# field_mill.net
KiCad netlist of a schematic drawn in EAGLE
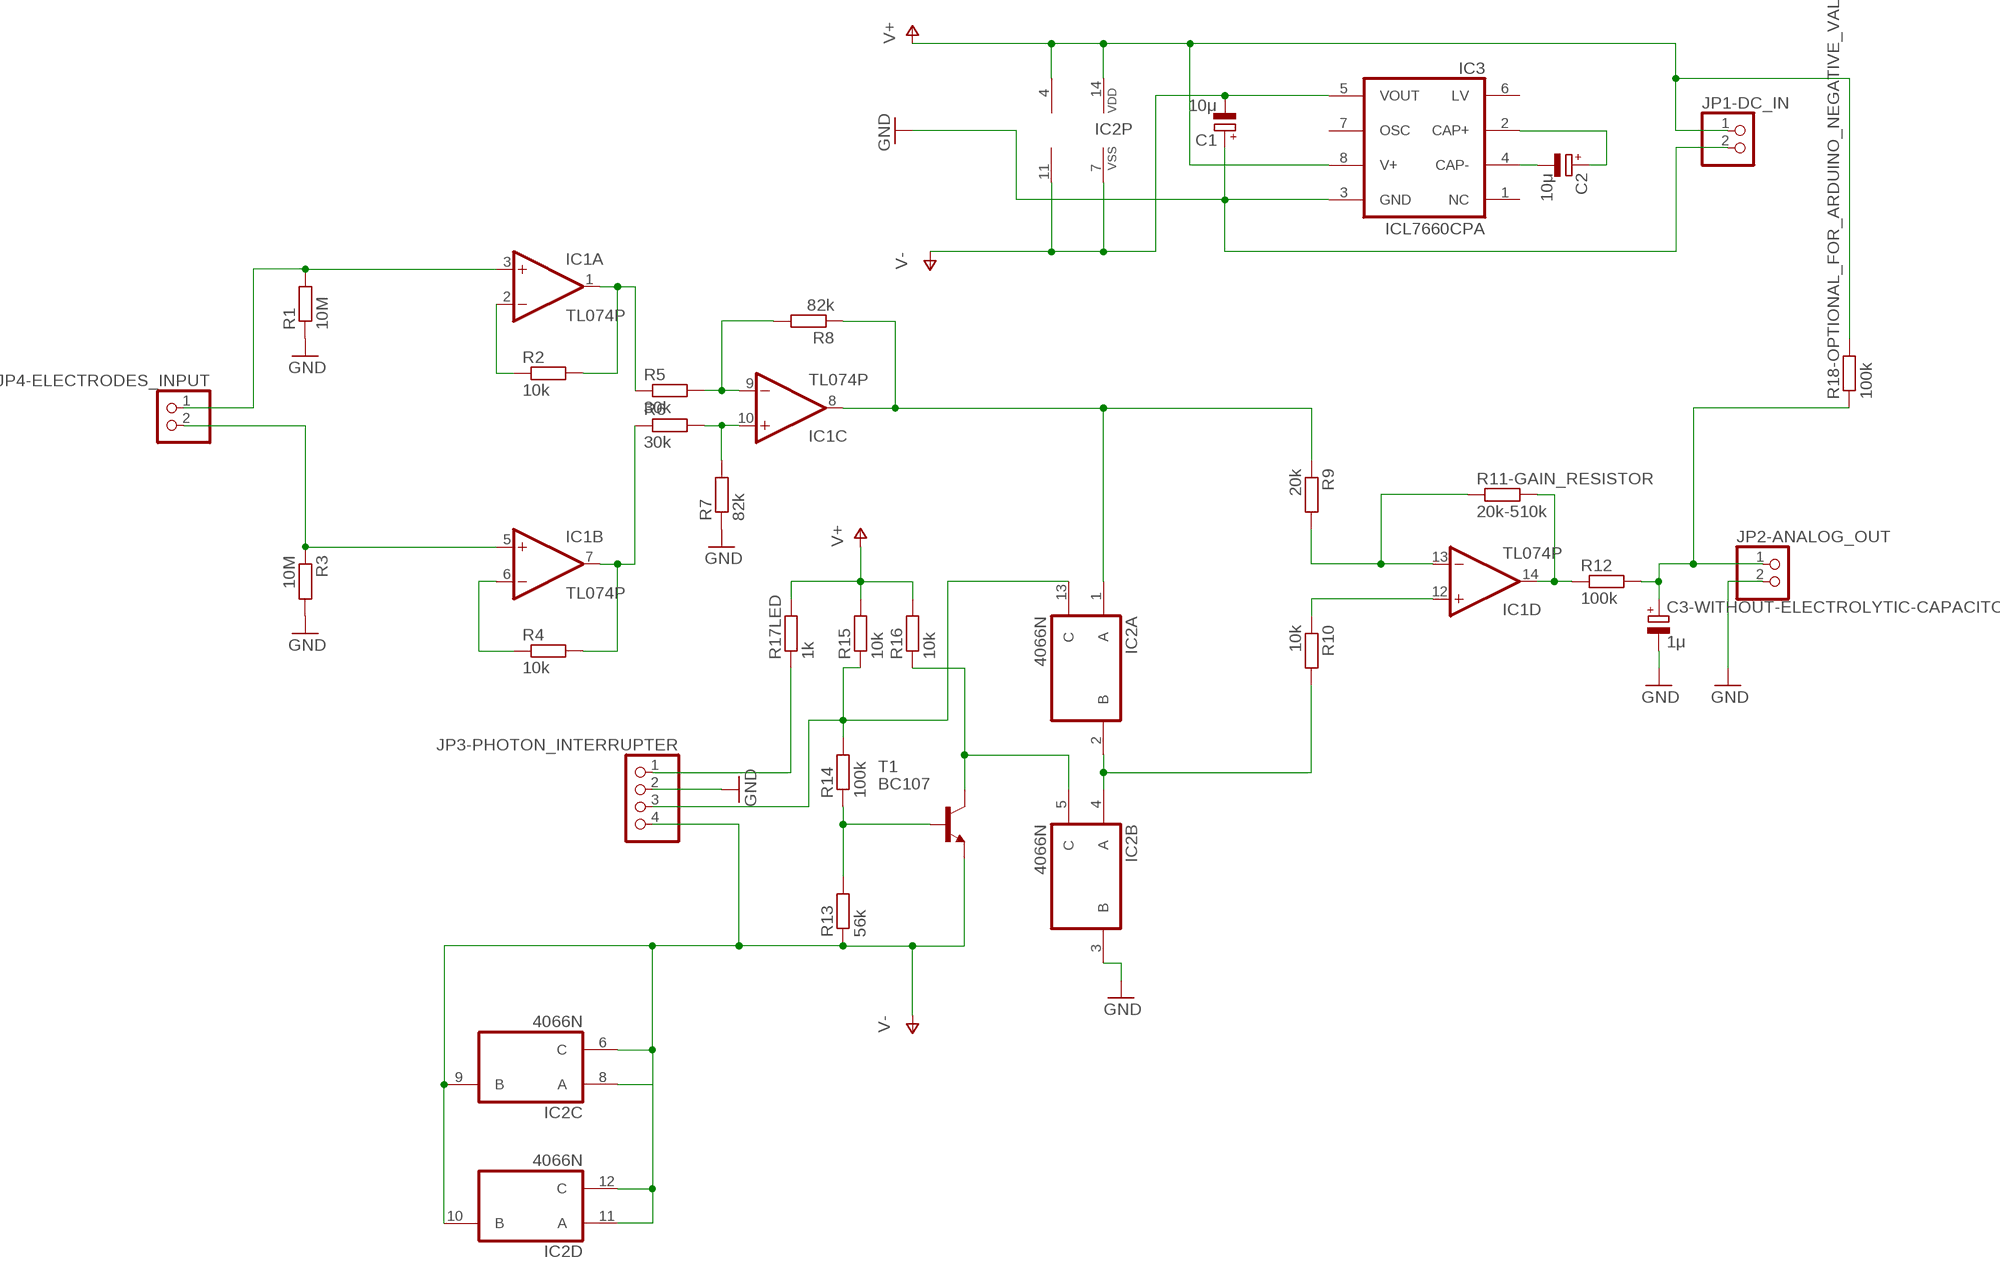
[diagram p0: schematic, sheet 1]

(export (version "E")
  (design (tool "Eeschema 10.0.6"))
  (components
    (comp (ref "C1")
      (value "10μ")
      (footprint "eagle-import:E2,5-6")
      (libsource (lib "eagle-import") (part "CPOL-EUE2.5-6"))
    )
    (comp (ref "C2")
      (value "10μ")
      (footprint "eagle-import:E2,5-6")
      (libsource (lib "eagle-import") (part "CPOL-EUE2.5-6"))
    )
    (comp (ref "C3-WITHOUT-ELECTROLYTIC-CAPACITOR")
      (value "1μ")
      (footprint "eagle-import:E2,5-6")
      (libsource (lib "eagle-import") (part "CPOL-EUE2.5-6"))
    )
    (comp (ref "IC1")
      (value "TL074P")
      (footprint "eagle-import:DIL14")
      (libsource (lib "eagle-import") (part "TL074P"))
    )
    (comp (ref "IC2")
      (value "4066N")
      (footprint "eagle-import:DIL14")
      (libsource (lib "eagle-import") (part "4066N"))
    )
    (comp (ref "IC3")
      (value "ICL7660CPA")
      (footprint "eagle-import:DIL08")
      (fields (field (name "MF") "INTERSIL"))
      (libsource (lib "eagle-import") (part "ICL7660CPA"))
    )
    (comp (ref "JP1-DC_IN")
      (value "PINHD-1X2")
      (footprint "eagle-import:1X02")
      (libsource (lib "eagle-import") (part "PINHD-1X2"))
    )
    (comp (ref "JP2-ANALOG_OUT")
      (value "PINHD-1X2")
      (footprint "eagle-import:1X02")
      (libsource (lib "eagle-import") (part "PINHD-1X2"))
    )
    (comp (ref "JP3-PHOTON_INTERRUPTER")
      (value "PINHD-1X4")
      (footprint "eagle-import:1X04")
      (libsource (lib "eagle-import") (part "PINHD-1X4"))
    )
    (comp (ref "JP4-ELECTRODES_INPUT")
      (value "PINHD-1X2")
      (footprint "eagle-import:1X02")
      (libsource (lib "eagle-import") (part "PINHD-1X2"))
    )
    (comp (ref "R1")
      (value "10M")
      (footprint "eagle-import:0207_10")
      (libsource (lib "eagle-import") (part "R-EU_0207/10"))
    )
    (comp (ref "R2")
      (value "10k")
      (footprint "eagle-import:0207_10")
      (libsource (lib "eagle-import") (part "R-EU_0207/10"))
    )
    (comp (ref "R3")
      (value "10M")
      (footprint "eagle-import:0207_10")
      (libsource (lib "eagle-import") (part "R-EU_0207/10"))
    )
    (comp (ref "R4")
      (value "10k")
      (footprint "eagle-import:0207_10")
      (libsource (lib "eagle-import") (part "R-EU_0207/10"))
    )
    (comp (ref "R5")
      (value "30k")
      (footprint "eagle-import:0207_10")
      (libsource (lib "eagle-import") (part "R-EU_0207/10"))
    )
    (comp (ref "R6")
      (value "30k")
      (footprint "eagle-import:0207_10")
      (libsource (lib "eagle-import") (part "R-EU_0207/10"))
    )
    (comp (ref "R7")
      (value "82k")
      (footprint "eagle-import:0207_10")
      (libsource (lib "eagle-import") (part "R-EU_0207/10"))
    )
    (comp (ref "R8")
      (value "82k")
      (footprint "eagle-import:0207_10")
      (libsource (lib "eagle-import") (part "R-EU_0207/10"))
    )
    (comp (ref "R9")
      (value "20k")
      (footprint "eagle-import:0207_10")
      (libsource (lib "eagle-import") (part "R-EU_0207/10"))
    )
    (comp (ref "R10")
      (value "10k")
      (footprint "eagle-import:0207_10")
      (libsource (lib "eagle-import") (part "R-EU_0207/10"))
    )
    (comp (ref "R11-GAIN_RESISTOR")
      (value "20k-510k")
      (footprint "eagle-import:0207_10")
      (libsource (lib "eagle-import") (part "R-EU_0207/10"))
    )
    (comp (ref "R12")
      (value "100k")
      (footprint "eagle-import:0207_10")
      (libsource (lib "eagle-import") (part "R-EU_0207/10"))
    )
    (comp (ref "R13")
      (value "56k")
      (footprint "eagle-import:0207_10")
      (libsource (lib "eagle-import") (part "R-EU_0207/10"))
    )
    (comp (ref "R14")
      (value "100k")
      (footprint "eagle-import:0207_10")
      (libsource (lib "eagle-import") (part "R-EU_0207/10"))
    )
    (comp (ref "R15")
      (value "10k")
      (footprint "eagle-import:0207_10")
      (libsource (lib "eagle-import") (part "R-EU_0207/10"))
    )
    (comp (ref "R16")
      (value "10k")
      (footprint "eagle-import:0207_10")
      (libsource (lib "eagle-import") (part "R-EU_0207/10"))
    )
    (comp (ref "R17LED")
      (value "1k")
      (footprint "eagle-import:0207_10")
      (libsource (lib "eagle-import") (part "R-EU_0207/10"))
    )
    (comp (ref "R18-OPTIONAL_FOR_ARDUINO_NEGATIVE_VALUES")
      (value "100k")
      (footprint "eagle-import:0207_10")
      (libsource (lib "eagle-import") (part "R-EU_0207/10"))
    )
    (comp (ref "T1")
      (value "BC107")
      (footprint "eagle-import:TO18")
      (libsource (lib "eagle-import") (part "BC107"))
    )
  )
  (nets
    (net (code "1") (name "GND") (class "Default")
      (node (ref "C1") (pin "+") (pinfunction "+_+") (pintype "passive"))
      (node (ref "C3-WITHOUT-ELECTROLYTIC-CAPACITOR") (pin "-") (pinfunction "-_-") (pintype "passive"))
      (node (ref "IC2") (pin "3") (pinfunction "B_3") (pintype "tri_state"))
      (node (ref "IC3") (pin "3") (pinfunction "GND_3") (pintype "power_in"))
      (node (ref "JP1-DC_IN") (pin "2") (pinfunction "2_2") (pintype "passive"))
      (node (ref "JP2-ANALOG_OUT") (pin "2") (pinfunction "2_2") (pintype "passive"))
      (node (ref "JP3-PHOTON_INTERRUPTER") (pin "2") (pinfunction "2_2") (pintype "passive"))
      (node (ref "R1") (pin "1") (pinfunction "1_1") (pintype "passive"))
      (node (ref "R3") (pin "2") (pinfunction "2_2") (pintype "passive"))
      (node (ref "R7") (pin "1") (pinfunction "1_1") (pintype "passive"))
    )
    (net (code "2") (name "Net-(C3-WITHOUT-ELECTROLYTIC-CAPACITOR-Pad+)") (class "Default")
      (node (ref "C3-WITHOUT-ELECTROLYTIC-CAPACITOR") (pin "+") (pinfunction "+_+") (pintype "passive"))
      (node (ref "JP2-ANALOG_OUT") (pin "1") (pinfunction "1_1") (pintype "passive"))
      (node (ref "R12") (pin "2") (pinfunction "2_2") (pintype "passive"))
      (node (ref "R18-OPTIONAL_FOR_ARDUINO_NEGATIVE_VALUES") (pin "1") (pinfunction "1_1") (pintype "passive"))
    )
    (net (code "3") (name "Net-(IC1A-+IN)") (class "Default")
      (node (ref "IC1") (pin "3") (pinfunction "+IN_3") (pintype "input"))
      (node (ref "JP4-ELECTRODES_INPUT") (pin "1") (pinfunction "1_1") (pintype "passive"))
      (node (ref "R1") (pin "2") (pinfunction "2_2") (pintype "passive"))
    )
    (net (code "4") (name "Net-(IC1A--IN)") (class "Default")
      (node (ref "IC1") (pin "2") (pinfunction "-IN_2") (pintype "input"))
      (node (ref "R2") (pin "1") (pinfunction "1_1") (pintype "passive"))
    )
    (net (code "5") (name "Net-(IC1A-OUT)") (class "Default")
      (node (ref "IC1") (pin "1") (pinfunction "OUT_1") (pintype "output"))
      (node (ref "R2") (pin "2") (pinfunction "2_2") (pintype "passive"))
      (node (ref "R5") (pin "1") (pinfunction "1_1") (pintype "passive"))
    )
    (net (code "6") (name "Net-(IC1B-+IN)") (class "Default")
      (node (ref "IC1") (pin "5") (pinfunction "+IN_5") (pintype "input"))
      (node (ref "JP4-ELECTRODES_INPUT") (pin "2") (pinfunction "2_2") (pintype "passive"))
      (node (ref "R3") (pin "1") (pinfunction "1_1") (pintype "passive"))
    )
    (net (code "7") (name "Net-(IC1B--IN)") (class "Default")
      (node (ref "IC1") (pin "6") (pinfunction "-IN_6") (pintype "input"))
      (node (ref "R4") (pin "1") (pinfunction "1_1") (pintype "passive"))
    )
    (net (code "8") (name "Net-(IC1B-OUT)") (class "Default")
      (node (ref "IC1") (pin "7") (pinfunction "OUT_7") (pintype "output"))
      (node (ref "R4") (pin "2") (pinfunction "2_2") (pintype "passive"))
      (node (ref "R6") (pin "1") (pinfunction "1_1") (pintype "passive"))
    )
    (net (code "9") (name "Net-(IC1C-+IN)") (class "Default")
      (node (ref "IC1") (pin "10") (pinfunction "+IN_10") (pintype "input"))
      (node (ref "R6") (pin "2") (pinfunction "2_2") (pintype "passive"))
      (node (ref "R7") (pin "2") (pinfunction "2_2") (pintype "passive"))
    )
    (net (code "10") (name "Net-(IC1C--IN)") (class "Default")
      (node (ref "IC1") (pin "9") (pinfunction "-IN_9") (pintype "input"))
      (node (ref "R5") (pin "2") (pinfunction "2_2") (pintype "passive"))
      (node (ref "R8") (pin "2") (pinfunction "2_2") (pintype "passive"))
    )
    (net (code "11") (name "Net-(IC1C-OUT)") (class "Default")
      (node (ref "IC1") (pin "8") (pinfunction "OUT_8") (pintype "output"))
      (node (ref "IC2") (pin "1") (pinfunction "A_1") (pintype "tri_state"))
      (node (ref "R8") (pin "1") (pinfunction "1_1") (pintype "passive"))
      (node (ref "R9") (pin "1") (pinfunction "1_1") (pintype "passive"))
    )
    (net (code "12") (name "Net-(IC1D-+IN)") (class "Default")
      (node (ref "IC1") (pin "12") (pinfunction "+IN_12") (pintype "input"))
      (node (ref "R10") (pin "1") (pinfunction "1_1") (pintype "passive"))
    )
    (net (code "13") (name "Net-(IC1D--IN)") (class "Default")
      (node (ref "IC1") (pin "13") (pinfunction "-IN_13") (pintype "input"))
      (node (ref "R11-GAIN_RESISTOR") (pin "1") (pinfunction "1_1") (pintype "passive"))
      (node (ref "R9") (pin "2") (pinfunction "2_2") (pintype "passive"))
    )
    (net (code "14") (name "Net-(IC1D-OUT)") (class "Default")
      (node (ref "IC1") (pin "14") (pinfunction "OUT_14") (pintype "output"))
      (node (ref "R11-GAIN_RESISTOR") (pin "2") (pinfunction "2_2") (pintype "passive"))
      (node (ref "R12") (pin "1") (pinfunction "1_1") (pintype "passive"))
    )
    (net (code "15") (name "Net-(IC2A-B)") (class "Default")
      (node (ref "IC2") (pin "2") (pinfunction "B_2") (pintype "tri_state"))
      (node (ref "IC2") (pin "4") (pinfunction "A_4") (pintype "tri_state"))
      (node (ref "R10") (pin "2") (pinfunction "2_2") (pintype "passive"))
    )
    (net (code "16") (name "Net-(IC2A-C)") (class "Default")
      (node (ref "IC2") (pin "13") (pinfunction "C_13") (pintype "input"))
      (node (ref "JP3-PHOTON_INTERRUPTER") (pin "3") (pinfunction "3_3") (pintype "passive"))
      (node (ref "R14") (pin "2") (pinfunction "2_2") (pintype "passive"))
      (node (ref "R15") (pin "1") (pinfunction "1_1") (pintype "passive"))
    )
    (net (code "17") (name "Net-(IC2B-C)") (class "Default")
      (node (ref "IC2") (pin "5") (pinfunction "C_5") (pintype "input"))
      (node (ref "R16") (pin "1") (pinfunction "1_1") (pintype "passive"))
      (node (ref "T1") (pin "3") (pinfunction "C_3") (pintype "passive"))
    )
    (net (code "18") (name "Net-(IC3-CAP+)") (class "Default")
      (node (ref "C2") (pin "+") (pinfunction "+_+") (pintype "passive"))
      (node (ref "IC3") (pin "2") (pinfunction "CAP+_2") (pintype "passive"))
    )
    (net (code "19") (name "Net-(IC3-CAP-)") (class "Default")
      (node (ref "C2") (pin "-") (pinfunction "-_-") (pintype "passive"))
      (node (ref "IC3") (pin "4") (pinfunction "CAP-_4") (pintype "passive"))
    )
    (net (code "20") (name "Net-(JP3-PHOTON_INTERRUPTER-Pad1)") (class "Default")
      (node (ref "JP3-PHOTON_INTERRUPTER") (pin "1") (pinfunction "1_1") (pintype "passive"))
      (node (ref "R17LED") (pin "1") (pinfunction "1_1") (pintype "passive"))
    )
    (net (code "21") (name "Net-(T1-B)") (class "Default")
      (node (ref "R13") (pin "2") (pinfunction "2_2") (pintype "passive"))
      (node (ref "R14") (pin "1") (pinfunction "1_1") (pintype "passive"))
      (node (ref "T1") (pin "2") (pinfunction "B_2") (pintype "passive"))
    )
    (net (code "22") (name "V+") (class "Default")
      (node (ref "IC1") (pin "4") (pinfunction "V+_4") (pintype "power_in"))
      (node (ref "IC2") (pin "14") (pinfunction "VDD_14") (pintype "power_in"))
      (node (ref "IC3") (pin "8") (pinfunction "V+_8") (pintype "power_in"))
      (node (ref "JP1-DC_IN") (pin "1") (pinfunction "1_1") (pintype "passive"))
      (node (ref "R15") (pin "2") (pinfunction "2_2") (pintype "passive"))
      (node (ref "R16") (pin "2") (pinfunction "2_2") (pintype "passive"))
      (node (ref "R17LED") (pin "2") (pinfunction "2_2") (pintype "passive"))
      (node (ref "R18-OPTIONAL_FOR_ARDUINO_NEGATIVE_VALUES") (pin "2") (pinfunction "2_2") (pintype "passive"))
    )
    (net (code "23") (name "V-") (class "Default")
      (node (ref "C1") (pin "-") (pinfunction "-_-") (pintype "passive"))
      (node (ref "IC1") (pin "11") (pinfunction "V-_11") (pintype "power_in"))
      (node (ref "IC2") (pin "10") (pinfunction "B_10") (pintype "tri_state"))
      (node (ref "IC2") (pin "11") (pinfunction "A_11") (pintype "tri_state"))
      (node (ref "IC2") (pin "12") (pinfunction "C_12") (pintype "input"))
      (node (ref "IC2") (pin "6") (pinfunction "C_6") (pintype "input"))
      (node (ref "IC2") (pin "7") (pinfunction "VSS_7") (pintype "power_in"))
      (node (ref "IC2") (pin "8") (pinfunction "A_8") (pintype "tri_state"))
      (node (ref "IC2") (pin "9") (pinfunction "B_9") (pintype "tri_state"))
      (node (ref "IC3") (pin "5") (pinfunction "VOUT_5") (pintype "output"))
      (node (ref "JP3-PHOTON_INTERRUPTER") (pin "4") (pinfunction "4_4") (pintype "passive"))
      (node (ref "R13") (pin "1") (pinfunction "1_1") (pintype "passive"))
      (node (ref "T1") (pin "1") (pinfunction "E_1") (pintype "passive"))
    )
    (net (code "24") (name "unconnected-(IC3-LV-Pad6)") (class "Default")
      (node (ref "IC3") (pin "6") (pinfunction "LV_6") (pintype "passive"))
    )
    (net (code "25") (name "unconnected-(IC3-NC-Pad1)") (class "Default")
      (node (ref "IC3") (pin "1") (pinfunction "NC_1") (pintype "no_connect"))
    )
    (net (code "26") (name "unconnected-(IC3-OSC-Pad7)") (class "Default")
      (node (ref "IC3") (pin "7") (pinfunction "OSC_7") (pintype "output"))
    )
  )
)
